# 1_1_7_Interface_board_GNSS.net
KiCad netlist of a schematic drawn in Altium Designer
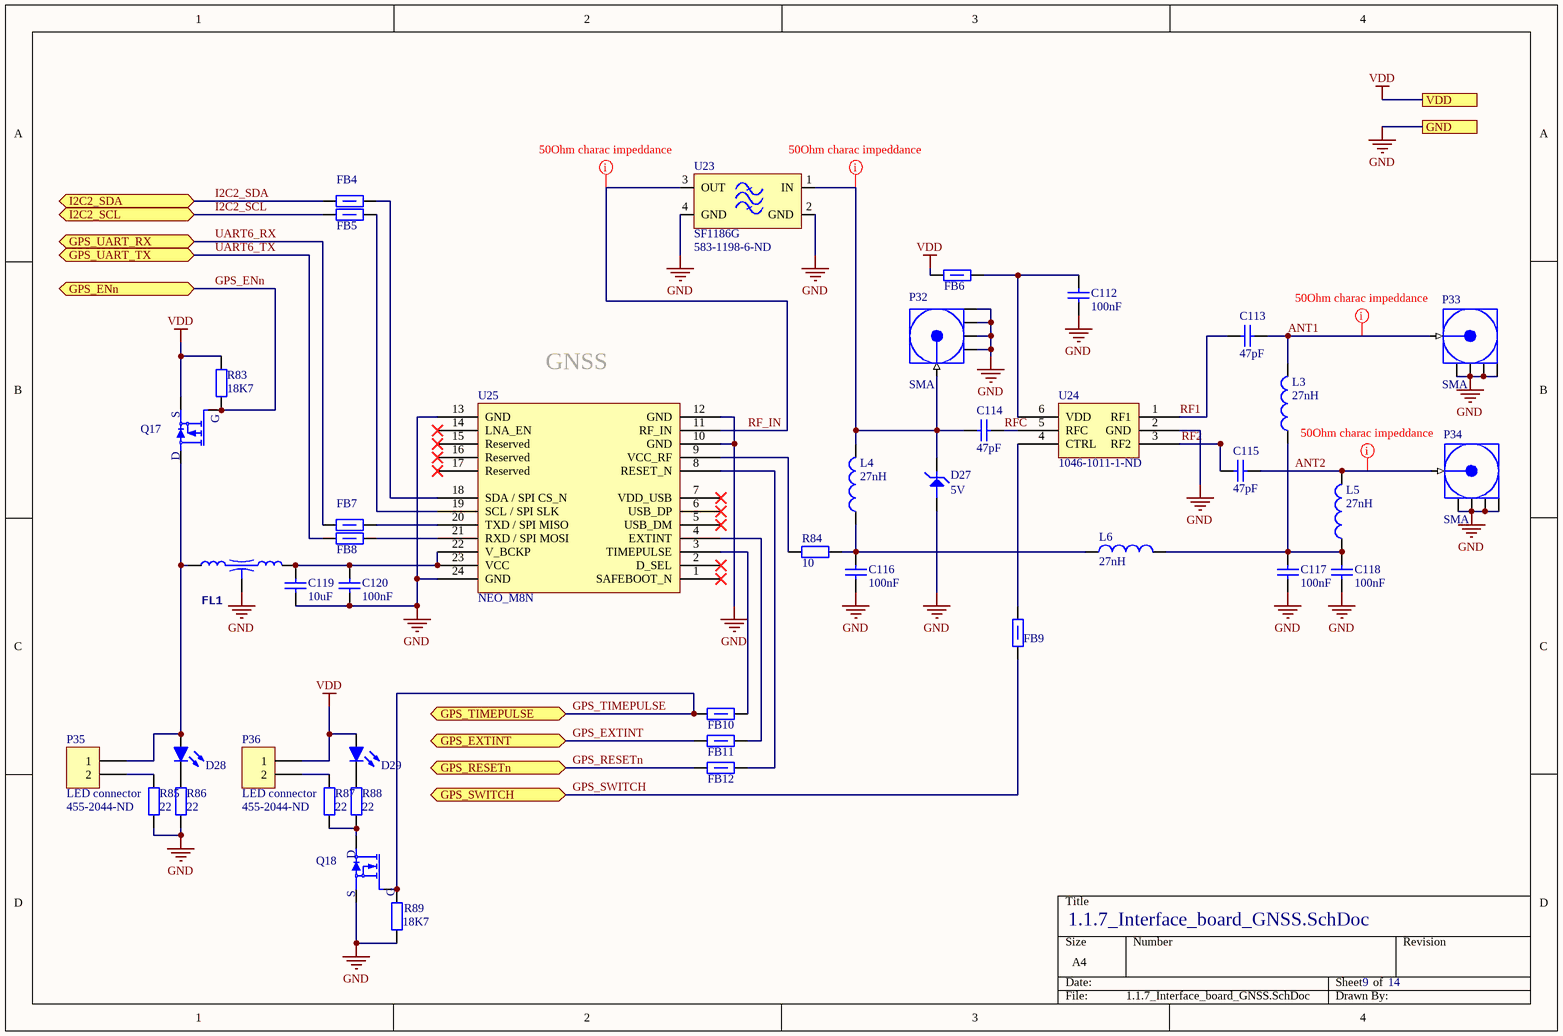
[diagram p0: 1.1.7_Interface_board_GNSS.SchDoc]

(export (version "E")
  (design (tool "Eeschema 10.0.6"))
  (components
    (comp (ref "C112")
      (value "100nF")
      (footprint "CAP0603R")
      (description "Capacitor")
      (libsource (lib "Rocket_library") (part "C_100nF"))
    )
    (comp (ref "C113")
      (value "47pF")
      (footprint "0402")
      (description "Capacitor")
      (libsource (lib "Rocket_library") (part "C_47pF_50V_0402"))
    )
    (comp (ref "C114")
      (value "47pF")
      (footprint "0402")
      (description "Capacitor")
      (libsource (lib "Rocket_library") (part "C_47pF_50V_0402"))
    )
    (comp (ref "C115")
      (value "47pF")
      (footprint "0402")
      (description "Capacitor")
      (libsource (lib "Rocket_library") (part "C_47pF_50V_0402"))
    )
    (comp (ref "C116")
      (value "100nF")
      (footprint "CAP0603R")
      (description "Capacitor")
      (libsource (lib "Rocket_library") (part "C_100nF"))
    )
    (comp (ref "C117")
      (value "100nF")
      (footprint "CAP0603R")
      (description "Capacitor")
      (libsource (lib "Rocket_library") (part "C_100nF"))
    )
    (comp (ref "C118")
      (value "100nF")
      (footprint "CAP0603R")
      (description "Capacitor")
      (libsource (lib "Rocket_library") (part "C_100nF"))
    )
    (comp (ref "C119")
      (value "10uF")
      (footprint "CAP0805W")
      (description "Capacitor")
      (libsource (lib "Rocket_library") (part "C_10uF_16v"))
    )
    (comp (ref "C120")
      (value "100nF")
      (footprint "CAP0603R")
      (description "Capacitor")
      (libsource (lib "Rocket_library") (part "C_100nF"))
    )
    (comp (ref "D27")
      (value "5V")
      (footprint "SOD-923")
      (description "Diodes TVS - Parasurtenseurs ESD")
      (libsource (lib "Rocket_library") (part "ESD9L5.0ST5G"))
    )
    (comp (ref "D28")
      (value "LED")
      (footprint "WL-SMCW")
      (description "Standard LEDs - SMD WL-SMCW Waterclr 0603 Green")
      (libsource (lib "Rocket_library") (part "LED_SMD_GREEN_0603"))
    )
    (comp (ref "D29")
      (value "LED")
      (footprint "WL-SMCW")
      (description "Standard LEDs - SMD WL-SMCW Waterclr 0603 Green")
      (libsource (lib "Rocket_library") (part "LED_SMD_GREEN_0603"))
    )
    (comp (ref "FB4")
      (value "81-BLM18KG601SZ1D")
      (footprint "0603")
      (libsource (lib "Rocket_library") (part "Ferrite_bead"))
    )
    (comp (ref "FB5")
      (value "81-BLM18KG601SZ1D")
      (footprint "0603")
      (libsource (lib "Rocket_library") (part "Ferrite_bead"))
    )
    (comp (ref "FB6")
      (value "81-BLM18KG601SZ1D")
      (footprint "0603")
      (libsource (lib "") (part "Ferrite_bead_2"))
    )
    (comp (ref "FB7")
      (value "81-BLM18KG601SZ1D")
      (footprint "0603")
      (libsource (lib "Rocket_library") (part "Ferrite_bead"))
    )
    (comp (ref "FB8")
      (value "81-BLM18KG601SZ1D")
      (footprint "0603")
      (libsource (lib "Rocket_library") (part "Ferrite_bead"))
    )
    (comp (ref "FB9")
      (value "81-BLM18KG601SZ1D")
      (footprint "0603")
      (libsource (lib "") (part "Ferrite_bead_1"))
    )
    (comp (ref "FB10")
      (value "81-BLM18KG601SZ1D")
      (footprint "0603")
      (libsource (lib "") (part "Ferrite_bead_2"))
    )
    (comp (ref "FB11")
      (value "81-BLM18KG601SZ1D")
      (footprint "0603")
      (libsource (lib "") (part "Ferrite_bead_2"))
    )
    (comp (ref "FB12")
      (value "81-BLM18KG601SZ1D")
      (footprint "0603")
      (libsource (lib "") (part "Ferrite_bead_2"))
    )
    (comp (ref "FL1")
      (value "NFE31P Series (1206 Size)   Chip EMIFILr LC Combined Type")
      (footprint "LCL_NFE31P")
      (libsource (lib "Rocket_library") (part "NFE31P"))
    )
    (comp (ref "L3")
      (value "27nH")
      (footprint "0402")
      (description "Inductor")
      (libsource (lib "Rocket_library") (part "L_27nH_0402"))
    )
    (comp (ref "L4")
      (value "27nH")
      (footprint "0402")
      (description "Inductor")
      (libsource (lib "Rocket_library") (part "L_27nH_0402"))
    )
    (comp (ref "L5")
      (value "27nH")
      (footprint "0402")
      (description "Inductor")
      (libsource (lib "Rocket_library") (part "L_27nH_0402"))
    )
    (comp (ref "L6")
      (value "27nH")
      (footprint "0402")
      (description "Inductor")
      (libsource (lib "Rocket_library") (part "L_27nH_0402"))
    )
    (comp (ref "P32")
      (value "SMA")
      (footprint "SMA_TH_VERTICAL_LONG")
      (description "Connecteurs coaxiaux SMA STRAIGHT JACK PCB MOUNT BULKHEAD")
      (libsource (lib "Rocket_library") (part "COAX_SMA_PCB"))
    )
    (comp (ref "P33")
      (value "SMA")
      (footprint "SMA_TH_VERTICAL_LONG")
      (description "Connecteurs coaxiaux SMA STRAIGHT JACK PCB MOUNT BULKHEAD")
      (libsource (lib "Rocket_library") (part "COAX_SMA_PCB"))
    )
    (comp (ref "P34")
      (value "SMA")
      (footprint "SMA_TH_VERTICAL_LONG")
      (description "Connecteurs coaxiaux SMA STRAIGHT JACK PCB MOUNT BULKHEAD")
      (libsource (lib "Rocket_library") (part "COAX_SMA_PCB"))
    )
    (comp (ref "P35")
      (value "LED connector")
      (footprint "CON_JST_XA_ S02B-XASS-1")
      (description "Header 2p JST XA 3A right angle")
      (fields (field (name "SUPPLIER PART NUMBER 1") "455-2044-ND"))
      (libsource (lib "Rocket_library") (part "Header 2p JST XA 3A right angle"))
    )
    (comp (ref "P36")
      (value "LED connector")
      (footprint "CON_JST_XA_ S02B-XASS-1")
      (description "Header 2p JST XA 3A right angle")
      (fields (field (name "SUPPLIER PART NUMBER 1") "455-2044-ND"))
      (libsource (lib "Rocket_library") (part "Header 2p JST XA 3A right angle"))
    )
    (comp (ref "Q17")
      (value "MOSFET_P")
      (footprint "SOT23")
      (description "MOSFET 40V P-channel Trench MOSFET SOT-23-3")
      (libsource (lib "Rocket_library") (part "MOSFET_P_ 20V_1.5A"))
    )
    (comp (ref "Q18")
      (value "MOSFET_N")
      (footprint "SOT-323-3")
      (description "MOSFET N-Ch 20V 1.4A SOT-323-3")
      (libsource (lib "Rocket_library") (part "MOSFET_N_ 20V_1.4A"))
    )
    (comp (ref "R83")
      (value "18K7")
      (footprint "0603")
      (description "0.1W 18K7")
      (libsource (lib "Rocket_library") (part "R_0603_01W_18K7"))
    )
    (comp (ref "R84")
      (value "10")
      (footprint "0603")
      (description "0.25W 10Ohm")
      (libsource (lib "Rocket_library") (part "R_0603_025W_10Ohm"))
    )
    (comp (ref "R85")
      (value "22")
      (footprint "0603")
      (description "0.25W 22Ohm")
      (libsource (lib "Rocket_library") (part "R_0603_025W_22Ohm"))
    )
    (comp (ref "R86")
      (value "22")
      (footprint "0603")
      (description "0.25W 22Ohm")
      (libsource (lib "Rocket_library") (part "R_0603_025W_22Ohm"))
    )
    (comp (ref "R87")
      (value "22")
      (footprint "0603")
      (description "0.25W 22Ohm")
      (libsource (lib "Rocket_library") (part "R_0603_025W_22Ohm"))
    )
    (comp (ref "R88")
      (value "22")
      (footprint "0603")
      (description "0.25W 22Ohm")
      (libsource (lib "Rocket_library") (part "R_0603_025W_22Ohm"))
    )
    (comp (ref "R89")
      (value "18K7")
      (footprint "0603")
      (description "0.1W 18K7")
      (libsource (lib "") (part "R_0603_01W_18K7_1"))
    )
    (comp (ref "U23")
      (value "SF1186G")
      (footprint "SMD_2.5X2MM_4P")
      (description "SAW GPS Filter")
      (fields (field (name "SUPPLIER PART NUMBER 1") "583-1198-6-ND"))
      (libsource (lib "Rocket_library") (part "SF1186G"))
    )
    (comp (ref "U24")
      (value "PE4259")
      (footprint "SC-70")
      (description "RF SWITCH")
      (fields (field (name "SUPPLIER PART NUMBER 1") "1046-1011-1-ND"))
      (libsource (lib "Rocket_library") (part "PE4259"))
    )
    (comp (ref "U25")
      (value "NEO_M8")
      (footprint "NEO-8")
      (description "GNSS")
      (fields (field (name "SUPPLIER PART NUMBER 1") "NEO_M8N"))
      (libsource (lib "Rocket_library") (part "uBlox_Neo M8"))
    )
  )
  (nets
    (net (code "1") (name "/ANT1") (class "Default")
      (node (ref "C113") (pin "1") (pinfunction "1_1") (pintype "passive"))
      (node (ref "L3") (pin "2") (pinfunction "2_2") (pintype "passive"))
      (node (ref "P33") (pin "1") (pinfunction "1_1") (pintype "input"))
    )
    (net (code "2") (name "/ANT2") (class "Default")
      (node (ref "C115") (pin "1") (pinfunction "1_1") (pintype "passive"))
      (node (ref "L5") (pin "2") (pinfunction "2_2") (pintype "passive"))
      (node (ref "P34") (pin "1") (pinfunction "1_1") (pintype "input"))
    )
    (net (code "3") (name "/GPS_ENn") (class "Default")
      (node (ref "Q17") (pin "1") (pinfunction "G_1") (pintype "passive"))
      (node (ref "R83") (pin "1") (pinfunction "1_1") (pintype "passive"))
    )
    (net (code "4") (name "/GPS_EXTINT") (class "Default")
      (node (ref "FB11") (pin "2") (pinfunction "2_2") (pintype "passive"))
    )
    (net (code "5") (name "/GPS_RESETn") (class "Default")
      (node (ref "FB12") (pin "2") (pinfunction "2_2") (pintype "passive"))
    )
    (net (code "6") (name "/GPS_SWITCH") (class "Default")
      (node (ref "FB9") (pin "1") (pinfunction "1_1") (pintype "passive"))
    )
    (net (code "7") (name "/GPS_TIMEPULSE") (class "Default")
      (node (ref "FB10") (pin "2") (pinfunction "2_2") (pintype "passive"))
      (node (ref "Q18") (pin "1") (pinfunction "G_1") (pintype "passive"))
      (node (ref "R89") (pin "1") (pinfunction "1_1") (pintype "passive"))
    )
    (net (code "8") (name "/I2C2_SCL") (class "Default")
      (node (ref "FB5") (pin "1") (pinfunction "1_1") (pintype "passive"))
    )
    (net (code "9") (name "/I2C2_SDA") (class "Default")
      (node (ref "FB4") (pin "1") (pinfunction "1_1") (pintype "passive"))
    )
    (net (code "10") (name "/RF1") (class "Default")
      (node (ref "C113") (pin "2") (pinfunction "2_2") (pintype "passive"))
      (node (ref "U24") (pin "1") (pinfunction "RF1_1") (pintype "passive"))
    )
    (net (code "11") (name "/RF2") (class "Default")
      (node (ref "C115") (pin "2") (pinfunction "2_2") (pintype "passive"))
      (node (ref "U24") (pin "3") (pinfunction "RF2_3") (pintype "passive"))
    )
    (net (code "12") (name "/RFC") (class "Default")
      (node (ref "C114") (pin "1") (pinfunction "1_1") (pintype "passive"))
      (node (ref "U24") (pin "5") (pinfunction "RFC_5") (pintype "passive"))
    )
    (net (code "13") (name "/RF_IN") (class "Default")
      (node (ref "U23") (pin "3") (pinfunction "OUT_3") (pintype "passive"))
      (node (ref "U25") (pin "11") (pinfunction "RF_IN_11") (pintype "passive"))
    )
    (net (code "14") (name "/UART6_RX") (class "Default")
      (node (ref "FB7") (pin "1") (pinfunction "1_1") (pintype "passive"))
    )
    (net (code "15") (name "/UART6_TX") (class "Default")
      (node (ref "FB8") (pin "1") (pinfunction "1_1") (pintype "passive"))
    )
    (net (code "16") (name "GND") (class "Default")
      (node (ref "C112") (pin "1") (pinfunction "1_1") (pintype "passive"))
      (node (ref "C116") (pin "1") (pinfunction "1_1") (pintype "passive"))
      (node (ref "C117") (pin "1") (pinfunction "1_1") (pintype "passive"))
      (node (ref "C118") (pin "1") (pinfunction "1_1") (pintype "passive"))
      (node (ref "C119") (pin "1") (pinfunction "1_1") (pintype "passive"))
      (node (ref "C120") (pin "1") (pinfunction "1_1") (pintype "passive"))
      (node (ref "D27") (pin "2") (pintype "passive"))
      (node (ref "FL1") (pin "2") (pinfunction "2_2") (pintype "passive"))
      (node (ref "P32") (pin "2") (pinfunction "2_2") (pintype "power_in"))
      (node (ref "P32") (pin "3") (pinfunction "3_3") (pintype "power_in"))
      (node (ref "P32") (pin "4") (pinfunction "4_4") (pintype "power_in"))
      (node (ref "P32") (pin "5") (pinfunction "5_5") (pintype "power_in"))
      (node (ref "P33") (pin "2") (pinfunction "2_2") (pintype "power_in"))
      (node (ref "P33") (pin "3") (pinfunction "3_3") (pintype "power_in"))
      (node (ref "P33") (pin "4") (pinfunction "4_4") (pintype "power_in"))
      (node (ref "P33") (pin "5") (pinfunction "5_5") (pintype "power_in"))
      (node (ref "P34") (pin "2") (pinfunction "2_2") (pintype "power_in"))
      (node (ref "P34") (pin "3") (pinfunction "3_3") (pintype "power_in"))
      (node (ref "P34") (pin "4") (pinfunction "4_4") (pintype "power_in"))
      (node (ref "P34") (pin "5") (pinfunction "5_5") (pintype "power_in"))
      (node (ref "Q18") (pin "2") (pinfunction "S_2") (pintype "passive"))
      (node (ref "R85") (pin "1") (pinfunction "1_1") (pintype "passive"))
      (node (ref "R86") (pin "1") (pinfunction "1_1") (pintype "passive"))
      (node (ref "R89") (pin "2") (pinfunction "2_2") (pintype "passive"))
      (node (ref "U23") (pin "2") (pinfunction "GND_2") (pintype "passive"))
      (node (ref "U23") (pin "4") (pinfunction "GND_4") (pintype "passive"))
      (node (ref "U24") (pin "2") (pinfunction "GND_2") (pintype "passive"))
      (node (ref "U25") (pin "10") (pinfunction "GND_10") (pintype "passive"))
      (node (ref "U25") (pin "12") (pinfunction "GND_12") (pintype "passive"))
      (node (ref "U25") (pin "13") (pinfunction "GND_13") (pintype "passive"))
      (node (ref "U25") (pin "24") (pinfunction "GND_24") (pintype "passive"))
    )
    (net (code "17") (name "Net-(C116-Pad2)") (class "Default")
      (node (ref "C116") (pin "2") (pinfunction "2_2") (pintype "passive"))
      (node (ref "L4") (pin "1") (pinfunction "1_1") (pintype "passive"))
      (node (ref "L6") (pin "1") (pinfunction "1_1") (pintype "passive"))
      (node (ref "R84") (pin "2") (pinfunction "2_2") (pintype "passive"))
    )
    (net (code "18") (name "Net-(C117-Pad2)") (class "Default")
      (node (ref "C117") (pin "2") (pinfunction "2_2") (pintype "passive"))
      (node (ref "C118") (pin "2") (pinfunction "2_2") (pintype "passive"))
      (node (ref "L3") (pin "1") (pinfunction "1_1") (pintype "passive"))
      (node (ref "L5") (pin "1") (pinfunction "1_1") (pintype "passive"))
      (node (ref "L6") (pin "2") (pinfunction "2_2") (pintype "passive"))
    )
    (net (code "19") (name "Net-(D28-PadC)") (class "Default")
      (node (ref "D28") (pin "C") (pinfunction "C_C") (pintype "passive"))
      (node (ref "R86") (pin "2") (pinfunction "2_2") (pintype "passive"))
    )
    (net (code "20") (name "Net-(D29-PadC)") (class "Default")
      (node (ref "D29") (pin "C") (pinfunction "C_C") (pintype "passive"))
      (node (ref "R88") (pin "2") (pinfunction "2_2") (pintype "passive"))
    )
    (net (code "21") (name "Net-(P35-Pad2)") (class "Default")
      (node (ref "P35") (pin "2") (pinfunction "2_2") (pintype "passive"))
      (node (ref "R85") (pin "2") (pinfunction "2_2") (pintype "passive"))
    )
    (net (code "22") (name "Net-(P36-Pad2)") (class "Default")
      (node (ref "P36") (pin "2") (pinfunction "2_2") (pintype "passive"))
      (node (ref "R87") (pin "2") (pinfunction "2_2") (pintype "passive"))
    )
    (net (code "23") (name "Net-(Q17-D)") (class "Default")
      (node (ref "D28") (pin "A") (pinfunction "A_A") (pintype "passive"))
      (node (ref "FL1") (pin "1") (pinfunction "1_1") (pintype "passive"))
      (node (ref "P35") (pin "1") (pinfunction "1_1") (pintype "passive"))
      (node (ref "Q17") (pin "3") (pinfunction "D_3") (pintype "passive"))
    )
    (net (code "24") (name "Net-(Q18-D)") (class "Default")
      (node (ref "Q18") (pin "3") (pinfunction "D_3") (pintype "passive"))
      (node (ref "R87") (pin "1") (pinfunction "1_1") (pintype "passive"))
      (node (ref "R88") (pin "1") (pinfunction "1_1") (pintype "passive"))
    )
    (net (code "25") (name "Net-(U23-IN)") (class "Default")
      (node (ref "C114") (pin "2") (pinfunction "2_2") (pintype "passive"))
      (node (ref "D27") (pin "1") (pintype "passive"))
      (node (ref "L4") (pin "2") (pinfunction "2_2") (pintype "passive"))
      (node (ref "P32") (pin "1") (pinfunction "1_1") (pintype "input"))
      (node (ref "U23") (pin "1") (pinfunction "IN_1") (pintype "passive"))
    )
    (net (code "26") (name "Net-(U24-CTRL)") (class "Default")
      (node (ref "FB9") (pin "2") (pinfunction "2_2") (pintype "passive"))
      (node (ref "U24") (pin "4") (pinfunction "CTRL_4") (pintype "passive"))
    )
    (net (code "27") (name "Net-(U24-VDD)") (class "Default")
      (node (ref "C112") (pin "2") (pinfunction "2_2") (pintype "passive"))
      (node (ref "FB6") (pin "1") (pinfunction "1_1") (pintype "passive"))
      (node (ref "U24") (pin "6") (pinfunction "VDD_6") (pintype "passive"))
    )
    (net (code "28") (name "Net-(U25-EXTINT)") (class "Default")
      (node (ref "FB11") (pin "1") (pinfunction "1_1") (pintype "passive"))
      (node (ref "U25") (pin "4") (pinfunction "EXTINT_4") (pintype "passive"))
    )
    (net (code "29") (name "Net-(U25-RESET_N)") (class "Default")
      (node (ref "FB12") (pin "1") (pinfunction "1_1") (pintype "passive"))
      (node (ref "U25") (pin "8") (pinfunction "RESET_N_8") (pintype "passive"))
    )
    (net (code "30") (name "Net-(U25-RXD_{slash}_SPI_MOSI)") (class "Default")
      (node (ref "FB8") (pin "2") (pinfunction "2_2") (pintype "passive"))
      (node (ref "U25") (pin "21") (pinfunction "RXD_/_SPI_MOSI_21") (pintype "passive"))
    )
    (net (code "31") (name "Net-(U25-SCL_{slash}_SPI_SLK)") (class "Default")
      (node (ref "FB5") (pin "2") (pinfunction "2_2") (pintype "passive"))
      (node (ref "U25") (pin "19") (pinfunction "SCL_/_SPI_SLK_19") (pintype "passive"))
    )
    (net (code "32") (name "Net-(U25-SDA_{slash}_SPI_CS_N)") (class "Default")
      (node (ref "FB4") (pin "2") (pinfunction "2_2") (pintype "passive"))
      (node (ref "U25") (pin "18") (pinfunction "SDA_/_SPI_CS_N_18") (pintype "passive"))
    )
    (net (code "33") (name "Net-(U25-TIMEPULSE)") (class "Default")
      (node (ref "FB10") (pin "1") (pinfunction "1_1") (pintype "passive"))
      (node (ref "U25") (pin "3") (pinfunction "TIMEPULSE_3") (pintype "passive"))
    )
    (net (code "34") (name "Net-(U25-TXD_{slash}_SPI_MISO)") (class "Default")
      (node (ref "FB7") (pin "2") (pinfunction "2_2") (pintype "passive"))
      (node (ref "U25") (pin "20") (pinfunction "TXD_/_SPI_MISO_20") (pintype "passive"))
    )
    (net (code "35") (name "Net-(U25-VCC)") (class "Default")
      (node (ref "C119") (pin "2") (pinfunction "2_2") (pintype "passive"))
      (node (ref "C120") (pin "2") (pinfunction "2_2") (pintype "passive"))
      (node (ref "FL1") (pin "3") (pinfunction "3_3") (pintype "passive"))
      (node (ref "U25") (pin "22") (pinfunction "V_BCKP_22") (pintype "passive"))
      (node (ref "U25") (pin "23") (pinfunction "VCC_23") (pintype "passive"))
    )
    (net (code "36") (name "Net-(U25-VCC_RF)") (class "Default")
      (node (ref "R84") (pin "1") (pinfunction "1_1") (pintype "passive"))
      (node (ref "U25") (pin "9") (pinfunction "VCC_RF_9") (pintype "passive"))
    )
    (net (code "37") (name "VDD") (class "Default")
      (node (ref "D29") (pin "A") (pinfunction "A_A") (pintype "passive"))
      (node (ref "FB6") (pin "2") (pinfunction "2_2") (pintype "passive"))
      (node (ref "P36") (pin "1") (pinfunction "1_1") (pintype "passive"))
      (node (ref "Q17") (pin "2") (pinfunction "S_2") (pintype "passive"))
      (node (ref "R83") (pin "2") (pinfunction "2_2") (pintype "passive"))
    )
    (net (code "38") (name "unconnected-(U25-D_SEL-Pad2)") (class "Default")
      (node (ref "U25") (pin "2") (pinfunction "D_SEL_2") (pintype "passive+no_connect"))
    )
    (net (code "39") (name "unconnected-(U25-LNA_EN-Pad14)") (class "Default")
      (node (ref "U25") (pin "14") (pinfunction "LNA_EN_14") (pintype "passive+no_connect"))
    )
    (net (code "40") (name "unconnected-(U25-Reserved-Pad15)") (class "Default")
      (node (ref "U25") (pin "15") (pinfunction "Reserved_15") (pintype "passive+no_connect"))
    )
    (net (code "41") (name "unconnected-(U25-Reserved-Pad16)") (class "Default")
      (node (ref "U25") (pin "16") (pinfunction "Reserved_16") (pintype "passive+no_connect"))
    )
    (net (code "42") (name "unconnected-(U25-Reserved-Pad17)") (class "Default")
      (node (ref "U25") (pin "17") (pinfunction "Reserved_17") (pintype "passive+no_connect"))
    )
    (net (code "43") (name "unconnected-(U25-SAFEBOOT_N-Pad1)") (class "Default")
      (node (ref "U25") (pin "1") (pinfunction "SAFEBOOT_N_1") (pintype "passive+no_connect"))
    )
    (net (code "44") (name "unconnected-(U25-USB_DM-Pad5)") (class "Default")
      (node (ref "U25") (pin "5") (pinfunction "USB_DM_5") (pintype "passive+no_connect"))
    )
    (net (code "45") (name "unconnected-(U25-USB_DP-Pad6)") (class "Default")
      (node (ref "U25") (pin "6") (pinfunction "USB_DP_6") (pintype "passive+no_connect"))
    )
    (net (code "46") (name "unconnected-(U25-VDD_USB-Pad7)") (class "Default")
      (node (ref "U25") (pin "7") (pinfunction "VDD_USB_7") (pintype "passive+no_connect"))
    )
  )
)
